# LDO.net
KiCad netlist of a schematic drawn in Altium Designer
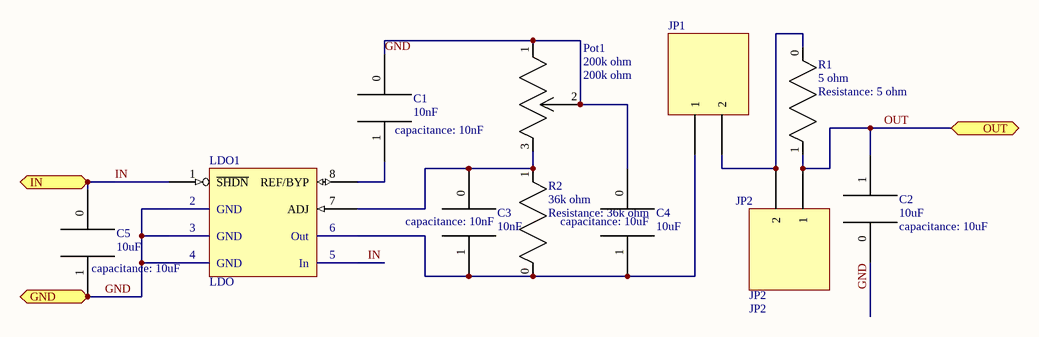
[diagram p0: LDO.SchDoc]

(export (version "E")
  (design (tool "Eeschema 10.0.6"))
  (components
    (comp (ref "C1")
      (value "10nF")
      (footprint "Capacitor")
      (description "0603cap")
      (fields (field (name "CAPACITANCE") "10nF"))
      (libsource (lib "Integrated_Library_Da2016") (part "cap"))
    )
    (comp (ref "C2")
      (value "10uF")
      (footprint "Capacitor")
      (description "0603cap")
      (fields (field (name "CAPACITANCE") "10uF"))
      (libsource (lib "Integrated_Library_Da2016") (part "cap"))
    )
    (comp (ref "C3")
      (value "10nF")
      (footprint "Capacitor")
      (description "0603cap")
      (fields (field (name "CAPACITANCE") "10nF"))
      (libsource (lib "Integrated_Library_Da2016") (part "cap"))
    )
    (comp (ref "C4")
      (value "10uF")
      (footprint "Capacitor")
      (description "0603cap")
      (fields (field (name "CAPACITANCE") "10uF"))
      (libsource (lib "Integrated_Library_Da2016") (part "cap"))
    )
    (comp (ref "C5")
      (value "10uF")
      (footprint "Capacitor")
      (description "0603cap")
      (fields (field (name "CAPACITANCE") "10uF"))
      (libsource (lib "Integrated_Library_Da2016") (part "cap"))
    )
    (comp (ref "JP1")
      (value "JP2")
      (footprint "JUMPER2")
      (description "Jumper_2")
      (libsource (lib "Integrated_Library_Da2016") (part "Jumper_2"))
    )
    (comp (ref "JP2")
      (value "JP2")
      (footprint "JUMPER2")
      (description "Jumper_2")
      (libsource (lib "") (part "Jumper_2_1"))
    )
    (comp (ref "LDO1")
      (value "LDO")
      (footprint "LT3060")
      (description "LT3060 LDO")
      (libsource (lib "Integrated_Library_Da2016") (part "LT3060"))
    )
    (comp (ref "Pot1")
      (value "200k ohm")
      (footprint "Pot")
      (description "Variable Resistor")
      (fields (field (name "RESISTANCE") "200k ohm"))
      (libsource (lib "Integrated_Library_Da2016") (part "Pot"))
    )
    (comp (ref "R1")
      (value "5 ohm")
      (footprint "Resistor")
      (description "0603Res")
      (fields (field (name "RESISTANCE") "5 ohm"))
      (libsource (lib "Integrated_Library_Da2016") (part "res"))
    )
    (comp (ref "R2")
      (value "36k ohm")
      (footprint "Resistor")
      (description "0603Res")
      (fields (field (name "RESISTANCE") "36k ohm"))
      (libsource (lib "Integrated_Library_Da2016") (part "res"))
    )
  )
  (nets
    (net (code "1") (name "/GND") (class "Default")
      (node (ref "C1") (pin "0") (pinfunction "0_0") (pintype "passive"))
      (node (ref "C2") (pin "0") (pinfunction "0_0") (pintype "passive"))
      (node (ref "C4") (pin "0") (pinfunction "0_0") (pintype "passive"))
      (node (ref "C5") (pin "1") (pinfunction "1_1") (pintype "passive"))
      (node (ref "LDO1") (pin "2") (pinfunction "GND_2") (pintype "power_in"))
      (node (ref "LDO1") (pin "3") (pinfunction "GND_3") (pintype "power_in"))
      (node (ref "LDO1") (pin "4") (pinfunction "GND_4") (pintype "power_in"))
      (node (ref "Pot1") (pin "1") (pinfunction "1_1") (pintype "passive"))
      (node (ref "Pot1") (pin "2") (pinfunction "2_2") (pintype "passive"))
    )
    (net (code "2") (name "/IN") (class "Default")
      (node (ref "C5") (pin "0") (pinfunction "0_0") (pintype "passive"))
      (node (ref "LDO1") (pin "1") (pinfunction "~{SHDN}_1") (pintype "input"))
      (node (ref "LDO1") (pin "5") (pinfunction "In_5") (pintype "power_in"))
    )
    (net (code "3") (name "/OUT") (class "Default")
      (node (ref "C2") (pin "1") (pinfunction "1_1") (pintype "passive"))
      (node (ref "JP2") (pin "1") (pinfunction "1_1") (pintype "passive"))
      (node (ref "R1") (pin "1") (pinfunction "1_1") (pintype "passive"))
    )
    (net (code "4") (name "Net-(JP1-Pad2)") (class "Default")
      (node (ref "JP1") (pin "2") (pinfunction "2_2") (pintype "passive"))
      (node (ref "JP2") (pin "2") (pinfunction "2_2") (pintype "passive"))
      (node (ref "R1") (pin "0") (pinfunction "0_0") (pintype "passive"))
    )
    (net (code "5") (name "Net-(LDO1-ADJ)") (class "Default")
      (node (ref "C3") (pin "0") (pinfunction "0_0") (pintype "passive"))
      (node (ref "LDO1") (pin "7") (pinfunction "ADJ_7") (pintype "input"))
      (node (ref "Pot1") (pin "3") (pinfunction "3_3") (pintype "passive"))
      (node (ref "R2") (pin "1") (pinfunction "1_1") (pintype "passive"))
    )
    (net (code "6") (name "Net-(LDO1-Out)") (class "Default")
      (node (ref "C3") (pin "1") (pinfunction "1_1") (pintype "passive"))
      (node (ref "C4") (pin "1") (pinfunction "1_1") (pintype "passive"))
      (node (ref "JP1") (pin "1") (pinfunction "1_1") (pintype "passive"))
      (node (ref "LDO1") (pin "6") (pinfunction "Out_6") (pintype "power_in"))
      (node (ref "R2") (pin "0") (pinfunction "0_0") (pintype "passive"))
    )
    (net (code "7") (name "Net-(LDO1-REF{slash}BYP)") (class "Default")
      (node (ref "C1") (pin "1") (pinfunction "1_1") (pintype "passive"))
      (node (ref "LDO1") (pin "8") (pinfunction "REF/BYP_8") (pintype "bidirectional"))
    )
  )
)
